# wall_power.net
KiCad netlist of a schematic drawn in EAGLE
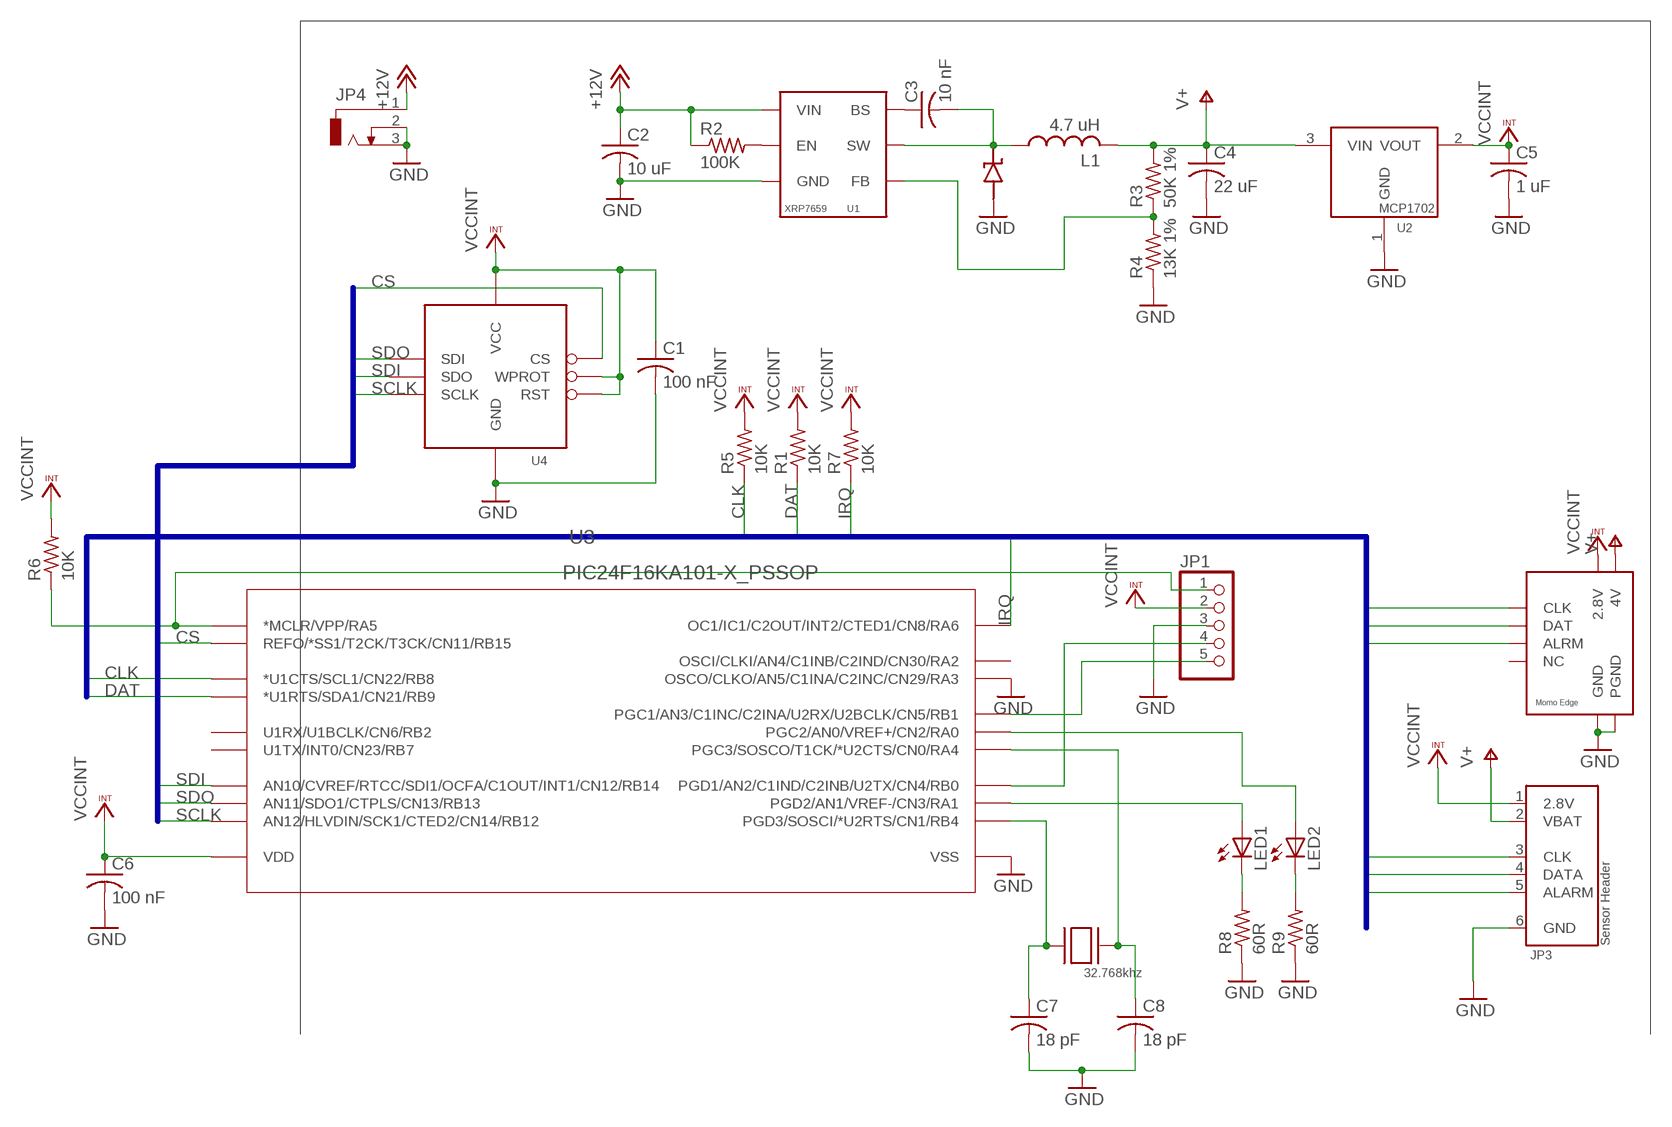
[diagram p0: schematic, sheet 1]

(export (version "E")
  (design (tool "Eeschema 10.0.6"))
  (components
    (comp (ref "C1")
      (value "100 nF")
      (footprint "eagle-import:C0402")
      (libsource (lib "eagle-import") (part "C-USC0402"))
    )
    (comp (ref "C2")
      (value "10 uF")
      (footprint "eagle-import:C0805")
      (libsource (lib "eagle-import") (part "C-USC0805"))
    )
    (comp (ref "C3")
      (value "10 nF")
      (footprint "eagle-import:C0402")
      (libsource (lib "eagle-import") (part "C-USC0402"))
    )
    (comp (ref "C4")
      (value "22 uF")
      (footprint "eagle-import:C1206")
      (libsource (lib "eagle-import") (part "C-USC1206"))
    )
    (comp (ref "C5")
      (value "1 uF")
      (footprint "eagle-import:C0402")
      (libsource (lib "eagle-import") (part "C-USC0402"))
    )
    (comp (ref "C6")
      (value "100 nF")
      (footprint "eagle-import:C0402")
      (libsource (lib "eagle-import") (part "C-USC0402"))
    )
    (comp (ref "C7")
      (value "18 pF")
      (footprint "eagle-import:C0402K")
      (libsource (lib "eagle-import") (part "C-USC0402K"))
    )
    (comp (ref "C8")
      (value "18 pF")
      (footprint "eagle-import:C0402K")
      (libsource (lib "eagle-import") (part "C-USC0402K"))
    )
    (comp (ref "D1")
      (value "DIODE_SS2P3SS2P3")
      (footprint "eagle-import:DIODE_SS2P3")
      (libsource (lib "eagle-import") (part "DIODE_SS2P3SS2P3"))
    )
    (comp (ref "JP1")
      (value "PINHD-1X5")
      (footprint "eagle-import:1X05")
      (libsource (lib "eagle-import") (part "PINHD-1X5"))
    )
    (comp (ref "JP2")
      (value "MOMO-EDGE-8F")
      (footprint "eagle-import:MOMO-EDGE-8F")
      (libsource (lib "eagle-import") (part "MOMO-EDGE-8F"))
    )
    (comp (ref "JP3")
      (value "MOMO-SENSOR-HEADER")
      (footprint "eagle-import:2X3-MOLEX-90130")
      (libsource (lib "eagle-import") (part "MOMO-SENSOR-HEADER"))
    )
    (comp (ref "JP4")
      (value "DCJ0303")
      (footprint "eagle-import:DCJ0303")
      (libsource (lib "eagle-import") (part "DCJ0303"))
    )
    (comp (ref "L1")
      (value "4.7 uH")
      (footprint "eagle-import:NR6028-INDUCTOR")
      (libsource (lib "eagle-import") (part "NR6028-INDUCTOR"))
    )
    (comp (ref "LED1")
      (value "LEDSML0603")
      (footprint "eagle-import:SML0603")
      (libsource (lib "eagle-import") (part "LEDSML0603"))
    )
    (comp (ref "LED2")
      (value "LEDSML0603")
      (footprint "eagle-import:SML0603")
      (libsource (lib "eagle-import") (part "LEDSML0603"))
    )
    (comp (ref "R1")
      (value "10K")
      (footprint "eagle-import:R0603")
      (libsource (lib "eagle-import") (part "R-US_R0603"))
    )
    (comp (ref "R2")
      (value "100K")
      (footprint "eagle-import:R0603")
      (libsource (lib "eagle-import") (part "R-US_R0603"))
    )
    (comp (ref "R3")
      (value "50K 1%")
      (footprint "eagle-import:R0603")
      (libsource (lib "eagle-import") (part "R-US_R0603"))
    )
    (comp (ref "R4")
      (value "13K 1%")
      (footprint "eagle-import:R0603")
      (libsource (lib "eagle-import") (part "R-US_R0603"))
    )
    (comp (ref "R5")
      (value "10K")
      (footprint "eagle-import:R0603")
      (libsource (lib "eagle-import") (part "R-US_R0603"))
    )
    (comp (ref "R6")
      (value "10K")
      (footprint "eagle-import:R0603")
      (libsource (lib "eagle-import") (part "R-US_R0603"))
    )
    (comp (ref "R7")
      (value "10K")
      (footprint "eagle-import:R0603")
      (libsource (lib "eagle-import") (part "R-US_R0603"))
    )
    (comp (ref "R8")
      (value "60R")
      (footprint "eagle-import:R0603")
      (libsource (lib "eagle-import") (part "R-US_R0603"))
    )
    (comp (ref "R9")
      (value "60R")
      (footprint "eagle-import:R0603")
      (libsource (lib "eagle-import") (part "R-US_R0603"))
    )
    (comp (ref "U1")
      (value "XRP7659")
      (footprint "eagle-import:SOT23-6L")
      (libsource (lib "eagle-import") (part "XRP7659"))
    )
    (comp (ref "U2")
      (value "MCP1702")
      (footprint "eagle-import:SOT23")
      (libsource (lib "eagle-import") (part "MCP1702"))
    )
    (comp (ref "U3")
      (value "PIC24F16KA101-X_PSSOP")
      (footprint "eagle-import:SSOP20")
      (libsource (lib "eagle-import") (part "PIC24F16KA101-X_PSSOP"))
    )
    (comp (ref "U4")
      (value "FLASH8MSOP8")
      (footprint "eagle-import:SOP08")
      (libsource (lib "eagle-import") (part "FLASH8MSOP8"))
    )
    (comp (ref "XTAL1")
      (value "32.768khz")
      (footprint "eagle-import:1206")
      (libsource (lib "eagle-import") (part "SMD-XTAL"))
    )
  )
  (nets
    (net (code "1") (name "+12V") (class "Default")
      (node (ref "C2") (pin "1") (pinfunction "1_1") (pintype "passive"))
      (node (ref "JP4") (pin "1") (pinfunction "1_1") (pintype "passive"))
      (node (ref "R2") (pin "1") (pinfunction "1_1") (pintype "passive"))
      (node (ref "U1") (pin "5") (pinfunction "VIN_5") (pintype "bidirectional"))
    )
    (net (code "2") (name "/CLK") (class "Default")
      (node (ref "JP2") (pin "CLK") (pinfunction "CLK_CLK") (pintype "bidirectional"))
      (node (ref "JP3") (pin "3") (pinfunction "CLK_3") (pintype "bidirectional"))
      (node (ref "R5") (pin "1") (pinfunction "1_1") (pintype "passive"))
      (node (ref "U3") (pin "12") (pinfunction "*U1CTS/SCL1/CN22/RB8_12") (pintype "bidirectional"))
    )
    (net (code "3") (name "/CS") (class "Default")
      (node (ref "U3") (pin "18") (pinfunction "REFO/*SS1/T2CK/T3CK/CN11/RB15_18") (pintype "bidirectional"))
      (node (ref "U4") (pin "1") (pinfunction "CS_1") (pintype "bidirectional"))
    )
    (net (code "4") (name "/DAT") (class "Default")
      (node (ref "JP2") (pin "DAT") (pinfunction "DAT_DAT") (pintype "bidirectional"))
      (node (ref "JP3") (pin "4") (pinfunction "DATA_4") (pintype "bidirectional"))
      (node (ref "R1") (pin "1") (pinfunction "1_1") (pintype "passive"))
      (node (ref "U3") (pin "13") (pinfunction "*U1RTS/SDA1/CN21/RB9_13") (pintype "bidirectional"))
    )
    (net (code "5") (name "/IRQ") (class "Default")
      (node (ref "JP2") (pin "ARLM") (pinfunction "ALRM_ARLM") (pintype "bidirectional"))
      (node (ref "JP3") (pin "5") (pinfunction "ALARM_5") (pintype "bidirectional"))
      (node (ref "R7") (pin "1") (pinfunction "1_1") (pintype "passive"))
      (node (ref "U3") (pin "14") (pinfunction "OC1/IC1/C2OUT/INT2/CTED1/CN8/RA6_14") (pintype "bidirectional"))
    )
    (net (code "6") (name "/SCLK") (class "Default")
      (node (ref "U3") (pin "15") (pinfunction "AN12/HLVDIN/SCK1/CTED2/CN14/RB12_15") (pintype "bidirectional"))
      (node (ref "U4") (pin "6") (pinfunction "SCLK_6") (pintype "bidirectional"))
    )
    (net (code "7") (name "/SDI") (class "Default")
      (node (ref "U3") (pin "17") (pinfunction "AN10/CVREF/RTCC/SDI1/OCFA/C1OUT/INT1/CN12/RB14_17") (pintype "bidirectional"))
      (node (ref "U4") (pin "2") (pinfunction "SDO_2") (pintype "bidirectional"))
    )
    (net (code "8") (name "/SDO") (class "Default")
      (node (ref "U3") (pin "16") (pinfunction "AN11/SDO1/CTPLS/CN13/RB13_16") (pintype "bidirectional"))
      (node (ref "U4") (pin "5") (pinfunction "SDI_5") (pintype "bidirectional"))
    )
    (net (code "9") (name "GND") (class "Default")
      (node (ref "C1") (pin "2") (pinfunction "2_2") (pintype "passive"))
      (node (ref "C2") (pin "2") (pinfunction "2_2") (pintype "passive"))
      (node (ref "C4") (pin "2") (pinfunction "2_2") (pintype "passive"))
      (node (ref "C5") (pin "2") (pinfunction "2_2") (pintype "passive"))
      (node (ref "C6") (pin "2") (pinfunction "2_2") (pintype "passive"))
      (node (ref "C7") (pin "2") (pinfunction "2_2") (pintype "passive"))
      (node (ref "C8") (pin "2") (pinfunction "2_2") (pintype "passive"))
      (node (ref "D1") (pin "AN") (pinfunction "AN_AN") (pintype "bidirectional"))
      (node (ref "JP1") (pin "3") (pinfunction "3_3") (pintype "passive"))
      (node (ref "JP2") (pin "GND") (pinfunction "GND_GND") (pintype "power_in"))
      (node (ref "JP2") (pin "PGND") (pinfunction "PGND_PGND") (pintype "power_in"))
      (node (ref "JP3") (pin "6") (pinfunction "GND_6") (pintype "bidirectional"))
      (node (ref "JP4") (pin "2") (pinfunction "2_2") (pintype "passive"))
      (node (ref "JP4") (pin "3") (pinfunction "3_3") (pintype "passive"))
      (node (ref "R4") (pin "1") (pinfunction "1_1") (pintype "passive"))
      (node (ref "R8") (pin "1") (pinfunction "1_1") (pintype "passive"))
      (node (ref "R9") (pin "1") (pinfunction "1_1") (pintype "passive"))
      (node (ref "U1") (pin "2") (pinfunction "GND_2") (pintype "bidirectional"))
      (node (ref "U2") (pin "1") (pinfunction "GND_1") (pintype "bidirectional"))
      (node (ref "U3") (pin "19") (pinfunction "VSS_19") (pintype "power_in"))
      (node (ref "U3") (pin "8") (pinfunction "OSCO/CLKO/AN5/C1INA/C2INC/CN29/RA3_8") (pintype "bidirectional"))
      (node (ref "U4") (pin "4") (pinfunction "GND_4") (pintype "power_in"))
    )
    (net (code "10") (name "Net-(LED1-PadC)") (class "Default")
      (node (ref "LED1") (pin "C") (pinfunction "C_C") (pintype "passive"))
      (node (ref "R8") (pin "2") (pinfunction "2_2") (pintype "passive"))
    )
    (net (code "11") (name "Net-(LED2-PadC)") (class "Default")
      (node (ref "LED2") (pin "C") (pinfunction "C_C") (pintype "passive"))
      (node (ref "R9") (pin "2") (pinfunction "2_2") (pintype "passive"))
    )
    (net (code "12") (name "Net-(U1-BS)") (class "Default")
      (node (ref "C3") (pin "1") (pinfunction "1_1") (pintype "passive"))
      (node (ref "U1") (pin "1") (pinfunction "BS_1") (pintype "bidirectional"))
    )
    (net (code "13") (name "Net-(U1-EN)") (class "Default")
      (node (ref "R2") (pin "2") (pinfunction "2_2") (pintype "passive"))
      (node (ref "U1") (pin "4") (pinfunction "EN_4") (pintype "bidirectional"))
    )
    (net (code "14") (name "Net-(U1-FB)") (class "Default")
      (node (ref "R3") (pin "1") (pinfunction "1_1") (pintype "passive"))
      (node (ref "R4") (pin "2") (pinfunction "2_2") (pintype "passive"))
      (node (ref "U1") (pin "3") (pinfunction "FB_3") (pintype "bidirectional"))
    )
    (net (code "15") (name "Net-(U1-SW)") (class "Default")
      (node (ref "C3") (pin "2") (pinfunction "2_2") (pintype "passive"))
      (node (ref "D1") (pin "CATH") (pinfunction "CATH_CATH") (pintype "bidirectional"))
      (node (ref "L1") (pin "1") (pinfunction "1_1") (pintype "passive"))
      (node (ref "U1") (pin "6") (pinfunction "SW_6") (pintype "bidirectional"))
    )
    (net (code "16") (name "Net-(U3-*MCLR{slash}VPP{slash}RA5)") (class "Default")
      (node (ref "JP1") (pin "1") (pinfunction "1_1") (pintype "passive"))
      (node (ref "R6") (pin "1") (pinfunction "1_1") (pintype "passive"))
      (node (ref "U3") (pin "1") (pinfunction "*MCLR/VPP/RA5_1") (pintype "bidirectional"))
    )
    (net (code "17") (name "Net-(U3-PGC1{slash}AN3{slash}C1INC{slash}C2INA{slash}U2RX{slash}U2BCLK{slash}CN5{slash}RB1)") (class "Default")
      (node (ref "JP1") (pin "5") (pinfunction "5_5") (pintype "passive"))
      (node (ref "U3") (pin "5") (pinfunction "PGC1/AN3/C1INC/C2INA/U2RX/U2BCLK/CN5/RB1_5") (pintype "bidirectional"))
    )
    (net (code "18") (name "Net-(U3-PGC2{slash}AN0{slash}VREF+{slash}CN2{slash}RA0)") (class "Default")
      (node (ref "LED2") (pin "A") (pinfunction "A_A") (pintype "passive"))
      (node (ref "U3") (pin "2") (pinfunction "PGC2/AN0/VREF+/CN2/RA0_2") (pintype "bidirectional"))
    )
    (net (code "19") (name "Net-(U3-PGC3{slash}SOSCO{slash}T1CK{slash}*U2CTS{slash}CN0{slash}RA4)") (class "Default")
      (node (ref "C8") (pin "1") (pinfunction "1_1") (pintype "passive"))
      (node (ref "U3") (pin "10") (pinfunction "PGC3/SOSCO/T1CK/*U2CTS/CN0/RA4_10") (pintype "bidirectional"))
      (node (ref "XTAL1") (pin "P$2") (pinfunction "XTAL2_P$2") (pintype "bidirectional"))
    )
    (net (code "20") (name "Net-(U3-PGD1{slash}AN2{slash}C1IND{slash}C2INB{slash}U2TX{slash}CN4{slash}RB0)") (class "Default")
      (node (ref "JP1") (pin "4") (pinfunction "4_4") (pintype "passive"))
      (node (ref "U3") (pin "4") (pinfunction "PGD1/AN2/C1IND/C2INB/U2TX/CN4/RB0_4") (pintype "bidirectional"))
    )
    (net (code "21") (name "Net-(U3-PGD2{slash}AN1{slash}VREF-{slash}CN3{slash}RA1)") (class "Default")
      (node (ref "LED1") (pin "A") (pinfunction "A_A") (pintype "passive"))
      (node (ref "U3") (pin "3") (pinfunction "PGD2/AN1/VREF-/CN3/RA1_3") (pintype "bidirectional"))
    )
    (net (code "22") (name "Net-(U3-PGD3{slash}SOSCI{slash}*U2RTS{slash}CN1{slash}RB4)") (class "Default")
      (node (ref "C7") (pin "1") (pinfunction "1_1") (pintype "passive"))
      (node (ref "U3") (pin "9") (pinfunction "PGD3/SOSCI/*U2RTS/CN1/RB4_9") (pintype "bidirectional"))
      (node (ref "XTAL1") (pin "P$1") (pinfunction "XTAL1_P$1") (pintype "bidirectional"))
    )
    (net (code "23") (name "V+") (class "Default")
      (node (ref "C4") (pin "1") (pinfunction "1_1") (pintype "passive"))
      (node (ref "JP2") (pin "V4.") (pinfunction "4V_V4.") (pintype "power_in"))
      (node (ref "JP3") (pin "2") (pinfunction "VBAT_2") (pintype "bidirectional"))
      (node (ref "L1") (pin "2") (pinfunction "2_2") (pintype "passive"))
      (node (ref "R3") (pin "2") (pinfunction "2_2") (pintype "passive"))
      (node (ref "U2") (pin "3") (pinfunction "VIN_3") (pintype "bidirectional"))
    )
    (net (code "24") (name "VCCINT") (class "Default")
      (node (ref "C1") (pin "1") (pinfunction "1_1") (pintype "passive"))
      (node (ref "C5") (pin "1") (pinfunction "1_1") (pintype "passive"))
      (node (ref "C6") (pin "1") (pinfunction "1_1") (pintype "passive"))
      (node (ref "JP1") (pin "2") (pinfunction "2_2") (pintype "passive"))
      (node (ref "JP2") (pin "V28") (pinfunction "2.8V_V28") (pintype "power_in"))
      (node (ref "JP3") (pin "1") (pinfunction "2.8V_1") (pintype "bidirectional"))
      (node (ref "R1") (pin "2") (pinfunction "2_2") (pintype "passive"))
      (node (ref "R5") (pin "2") (pinfunction "2_2") (pintype "passive"))
      (node (ref "R6") (pin "2") (pinfunction "2_2") (pintype "passive"))
      (node (ref "R7") (pin "2") (pinfunction "2_2") (pintype "passive"))
      (node (ref "U2") (pin "2") (pinfunction "VOUT_2") (pintype "bidirectional"))
      (node (ref "U3") (pin "20") (pinfunction "VDD_20") (pintype "power_in"))
      (node (ref "U4") (pin "3") (pinfunction "WPROT_3") (pintype "bidirectional"))
      (node (ref "U4") (pin "7") (pinfunction "RST_7") (pintype "bidirectional"))
      (node (ref "U4") (pin "8") (pinfunction "VCC_8") (pintype "power_in"))
    )
    (net (code "25") (name "unconnected-(JP2-NC-PadNV)") (class "Default")
      (node (ref "JP2") (pin "NV") (pinfunction "NC_NV") (pintype "bidirectional"))
    )
    (net (code "26") (name "unconnected-(U3-OSCI{slash}CLKI{slash}AN4{slash}C1INB{slash}C2IND{slash}CN30{slash}RA2-Pad7)") (class "Default")
      (node (ref "U3") (pin "7") (pinfunction "OSCI/CLKI/AN4/C1INB/C2IND/CN30/RA2_7") (pintype "bidirectional"))
    )
    (net (code "27") (name "unconnected-(U3-U1RX{slash}U1BCLK{slash}CN6{slash}RB2-Pad6)") (class "Default")
      (node (ref "U3") (pin "6") (pinfunction "U1RX/U1BCLK/CN6/RB2_6") (pintype "bidirectional"))
    )
    (net (code "28") (name "unconnected-(U3-U1TX{slash}INT0{slash}CN23{slash}RB7-Pad11)") (class "Default")
      (node (ref "U3") (pin "11") (pinfunction "U1TX/INT0/CN23/RB7_11") (pintype "bidirectional"))
    )
  )
)
